# ATmega.net
KiCad netlist of a schematic drawn in EAGLE
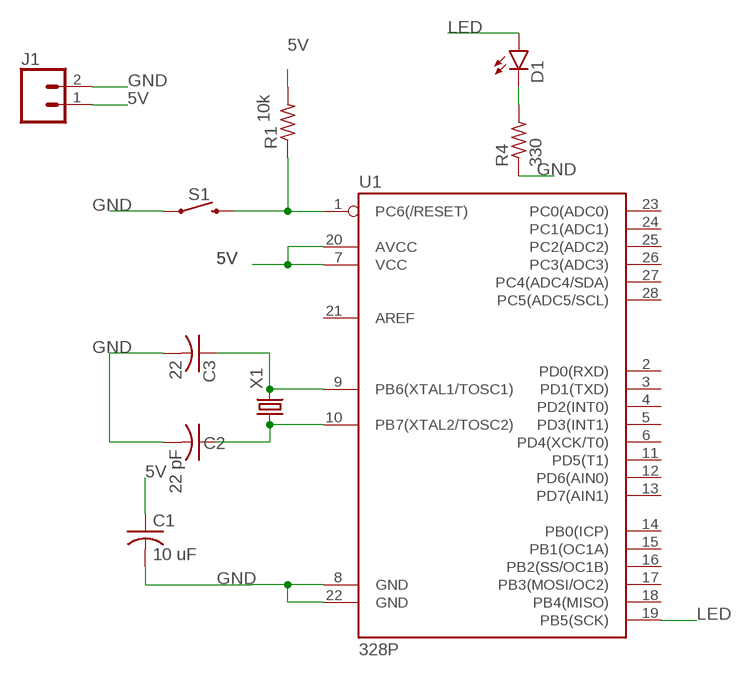
[diagram p0: schematic, sheet 1]

(export (version "E")
  (design (tool "Eeschema 10.0.6"))
  (components
    (comp (ref "C1")
      (value "10 uF")
      (footprint "eagle-import:C025-025X050")
      (libsource (lib "eagle-import") (part "C-US025-025X050"))
    )
    (comp (ref "C2")
      (value "22 pF")
      (footprint "eagle-import:C025-025X050")
      (libsource (lib "eagle-import") (part "C-US025-025X050"))
    )
    (comp (ref "C3")
      (value "22")
      (footprint "eagle-import:C025-025X050")
      (libsource (lib "eagle-import") (part "C-US025-025X050"))
    )
    (comp (ref "D1")
      (value "BEAGLEBONE_BLUE_LED-3MM-NO_SILK")
      (footprint "eagle-import:BEAGLEBONE_BLUE_BEAGLEBONE_BLUE_LED3MM-NS")
      (libsource (lib "eagle-import") (part "BEAGLEBONE_BLUE_LED-3MM-NO_SILK"))
    )
    (comp (ref "J1")
      (value "CONN_02")
      (footprint "eagle-import:1X02")
      (libsource (lib "eagle-import") (part "CONN_02"))
    )
    (comp (ref "R1")
      (value "R-US_0204/7")
      (footprint "eagle-import:0204_7")
      (fields (field (name "SPICEPREFIX") "R") (field (name "SPICEPREFIX_1") "10k"))
      (libsource (lib "eagle-import") (part "R-US_0204/7"))
    )
    (comp (ref "R4")
      (value "330")
      (footprint "eagle-import:0204_7")
      (libsource (lib "eagle-import") (part "R-US_0204/7"))
    )
    (comp (ref "S1")
      (value "MOMENTARY-SWITCH-SPST-PTH-6.0MM")
      (footprint "eagle-import:TACTILE_SWITCH_PTH_6.0MM")
      (libsource (lib "eagle-import") (part "MOMENTARY-SWITCH-SPST-PTH-6.0MM"))
    )
    (comp (ref "U1")
      (value "328P")
      (footprint "eagle-import:DIP28")
      (libsource (lib "eagle-import") (part "ATMEGA328P_PDIP"))
    )
    (comp (ref "X1")
      (value "CRYSTALS-NOGND-HC49")
      (footprint "eagle-import:HC49")
      (fields (field (name "POPULARITY") "16MHZ"))
      (libsource (lib "eagle-import") (part "CRYSTALS-NOGND-HC49"))
    )
  )
  (nets
    (net (code "1") (name "/5V") (class "Default")
      (node (ref "C1") (pin "1") (pinfunction "1_1") (pintype "passive"))
      (node (ref "J1") (pin "1") (pinfunction "1_1") (pintype "passive"))
      (node (ref "R1") (pin "2") (pinfunction "2_2") (pintype "passive"))
      (node (ref "U1") (pin "20") (pinfunction "AVCC_20") (pintype "bidirectional"))
      (node (ref "U1") (pin "7") (pinfunction "VCC_7") (pintype "bidirectional"))
    )
    (net (code "2") (name "/GND") (class "Default")
      (node (ref "C1") (pin "2") (pinfunction "2_2") (pintype "passive"))
      (node (ref "C2") (pin "2") (pinfunction "2_2") (pintype "passive"))
      (node (ref "C3") (pin "2") (pinfunction "2_2") (pintype "passive"))
      (node (ref "J1") (pin "2") (pinfunction "2_2") (pintype "passive"))
      (node (ref "R4") (pin "1") (pinfunction "1_1") (pintype "passive"))
      (node (ref "S1") (pin "1") (pinfunction "1_1") (pintype "passive"))
      (node (ref "U1") (pin "22") (pinfunction "GND_22") (pintype "bidirectional"))
      (node (ref "U1") (pin "8") (pinfunction "GND_8") (pintype "bidirectional"))
    )
    (net (code "3") (name "/LED") (class "Default")
      (node (ref "D1") (pin "A") (pinfunction "A_A") (pintype "passive"))
      (node (ref "U1") (pin "19") (pinfunction "PB5(SCK)_19") (pintype "bidirectional"))
    )
    (net (code "4") (name "Net-(D1-C)") (class "Default")
      (node (ref "D1") (pin "K") (pinfunction "C_K") (pintype "passive"))
      (node (ref "R4") (pin "2") (pinfunction "2_2") (pintype "passive"))
    )
    (net (code "5") (name "Net-(S1-2)") (class "Default")
      (node (ref "R1") (pin "1") (pinfunction "1_1") (pintype "passive"))
      (node (ref "S1") (pin "3") (pinfunction "2_3") (pintype "passive"))
      (node (ref "U1") (pin "1") (pinfunction "PC6(/RESET)_1") (pintype "bidirectional"))
    )
    (net (code "6") (name "Net-(U1-PB6(XTAL1{slash}TOSC1))") (class "Default")
      (node (ref "C3") (pin "1") (pinfunction "1_1") (pintype "passive"))
      (node (ref "U1") (pin "9") (pinfunction "PB6(XTAL1/TOSC1)_9") (pintype "bidirectional"))
      (node (ref "X1") (pin "2") (pinfunction "2_2") (pintype "passive"))
    )
    (net (code "7") (name "Net-(U1-PB7(XTAL2{slash}TOSC2))") (class "Default")
      (node (ref "C2") (pin "1") (pinfunction "1_1") (pintype "passive"))
      (node (ref "U1") (pin "10") (pinfunction "PB7(XTAL2/TOSC2)_10") (pintype "bidirectional"))
      (node (ref "X1") (pin "1") (pinfunction "1_1") (pintype "passive"))
    )
    (net (code "8") (name "unconnected-(U1-AREF-Pad21)") (class "Default")
      (node (ref "U1") (pin "21") (pinfunction "AREF_21") (pintype "bidirectional"))
    )
    (net (code "9") (name "unconnected-(U1-PB0(ICP)-Pad14)") (class "Default")
      (node (ref "U1") (pin "14") (pinfunction "PB0(ICP)_14") (pintype "bidirectional"))
    )
    (net (code "10") (name "unconnected-(U1-PB1(OC1A)-Pad15)") (class "Default")
      (node (ref "U1") (pin "15") (pinfunction "PB1(OC1A)_15") (pintype "bidirectional"))
    )
    (net (code "11") (name "unconnected-(U1-PB2(SS{slash}OC1B)-Pad16)") (class "Default")
      (node (ref "U1") (pin "16") (pinfunction "PB2(SS/OC1B)_16") (pintype "bidirectional"))
    )
    (net (code "12") (name "unconnected-(U1-PB3(MOSI{slash}OC2)-Pad17)") (class "Default")
      (node (ref "U1") (pin "17") (pinfunction "PB3(MOSI/OC2)_17") (pintype "bidirectional"))
    )
    (net (code "13") (name "unconnected-(U1-PB4(MISO)-Pad18)") (class "Default")
      (node (ref "U1") (pin "18") (pinfunction "PB4(MISO)_18") (pintype "bidirectional"))
    )
    (net (code "14") (name "unconnected-(U1-PC0(ADC0)-Pad23)") (class "Default")
      (node (ref "U1") (pin "23") (pinfunction "PC0(ADC0)_23") (pintype "bidirectional"))
    )
    (net (code "15") (name "unconnected-(U1-PC1(ADC1)-Pad24)") (class "Default")
      (node (ref "U1") (pin "24") (pinfunction "PC1(ADC1)_24") (pintype "bidirectional"))
    )
    (net (code "16") (name "unconnected-(U1-PC2(ADC2)-Pad25)") (class "Default")
      (node (ref "U1") (pin "25") (pinfunction "PC2(ADC2)_25") (pintype "bidirectional"))
    )
    (net (code "17") (name "unconnected-(U1-PC3(ADC3)-Pad26)") (class "Default")
      (node (ref "U1") (pin "26") (pinfunction "PC3(ADC3)_26") (pintype "bidirectional"))
    )
    (net (code "18") (name "unconnected-(U1-PC4(ADC4{slash}SDA)-Pad27)") (class "Default")
      (node (ref "U1") (pin "27") (pinfunction "PC4(ADC4/SDA)_27") (pintype "bidirectional"))
    )
    (net (code "19") (name "unconnected-(U1-PC5(ADC5{slash}SCL)-Pad28)") (class "Default")
      (node (ref "U1") (pin "28") (pinfunction "PC5(ADC5/SCL)_28") (pintype "bidirectional"))
    )
    (net (code "20") (name "unconnected-(U1-PD0(RXD)-Pad2)") (class "Default")
      (node (ref "U1") (pin "2") (pinfunction "PD0(RXD)_2") (pintype "bidirectional"))
    )
    (net (code "21") (name "unconnected-(U1-PD1(TXD)-Pad3)") (class "Default")
      (node (ref "U1") (pin "3") (pinfunction "PD1(TXD)_3") (pintype "bidirectional"))
    )
    (net (code "22") (name "unconnected-(U1-PD2(INT0)-Pad4)") (class "Default")
      (node (ref "U1") (pin "4") (pinfunction "PD2(INT0)_4") (pintype "bidirectional"))
    )
    (net (code "23") (name "unconnected-(U1-PD3(INT1)-Pad5)") (class "Default")
      (node (ref "U1") (pin "5") (pinfunction "PD3(INT1)_5") (pintype "bidirectional"))
    )
    (net (code "24") (name "unconnected-(U1-PD4(XCK{slash}T0)-Pad6)") (class "Default")
      (node (ref "U1") (pin "6") (pinfunction "PD4(XCK/T0)_6") (pintype "bidirectional"))
    )
    (net (code "25") (name "unconnected-(U1-PD5(T1)-Pad11)") (class "Default")
      (node (ref "U1") (pin "11") (pinfunction "PD5(T1)_11") (pintype "bidirectional"))
    )
    (net (code "26") (name "unconnected-(U1-PD6(AIN0)-Pad12)") (class "Default")
      (node (ref "U1") (pin "12") (pinfunction "PD6(AIN0)_12") (pintype "bidirectional"))
    )
    (net (code "27") (name "unconnected-(U1-PD7(AIN1)-Pad13)") (class "Default")
      (node (ref "U1") (pin "13") (pinfunction "PD7(AIN1)_13") (pintype "bidirectional"))
    )
  )
)
